# STM32H743.net
KiCad netlist of a schematic drawn in Altium Designer
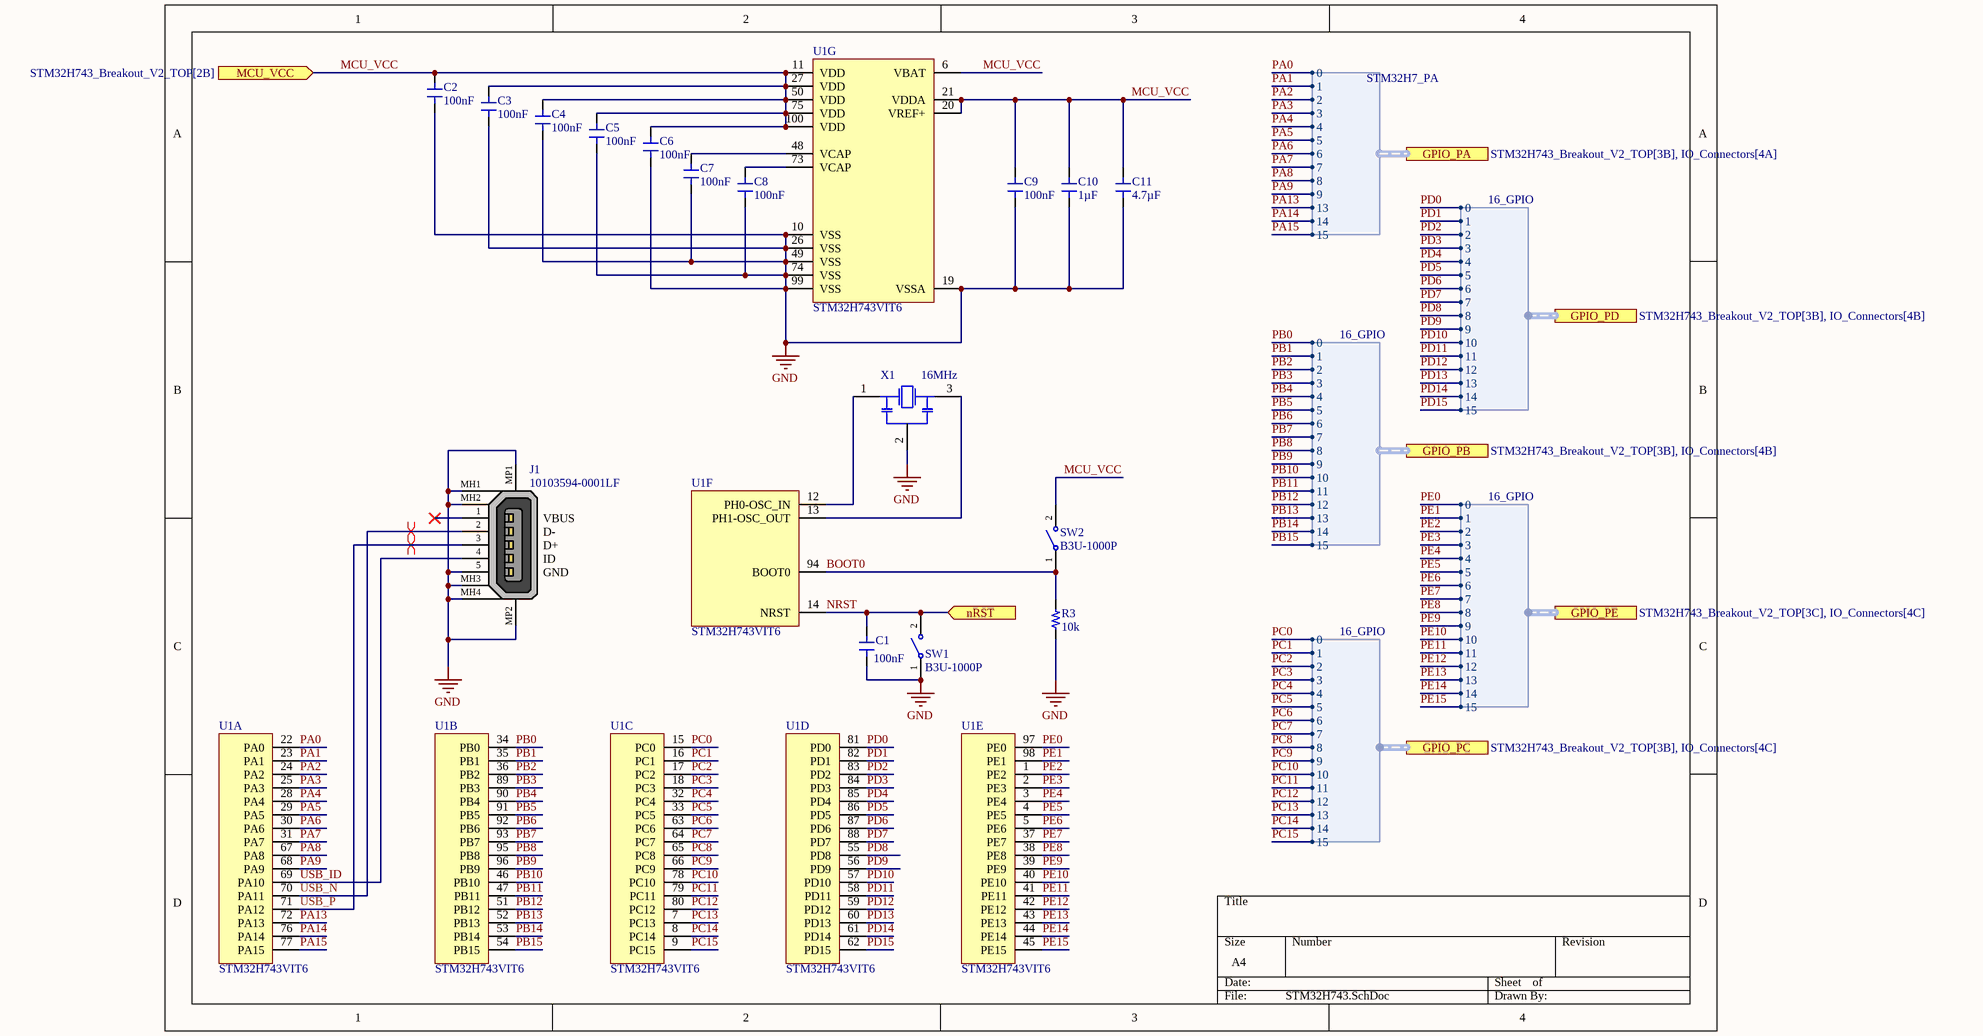
[diagram p0: STM32H743.SchDoc]

(export (version "E")
  (design (tool "Eeschema 10.0.6"))
  (components
    (comp (ref "C1")
      (value "C 0603 100nF 10% 50V X7R")
      (footprint "C-0603")
      (description "SMD Capacitor, Ceramic")
      (fields
        (field (name "CAPACITANCE") "100nF")
        (field (name "VOLTAGE") "50V")
        (field (name "TOLERANCE") "10%")
      )
      (libsource (lib "Project Rapid - Bruin Space") (part "Capacitor-NP"))
    )
    (comp (ref "C2")
      (value "C 0603 100nF 10% 50V X7R")
      (footprint "C-0603")
      (description "SMD Capacitor, Ceramic")
      (fields
        (field (name "CAPACITANCE") "100nF")
        (field (name "VOLTAGE") "50V")
        (field (name "TOLERANCE") "10%")
      )
      (libsource (lib "Project Rapid - Bruin Space") (part "Capacitor-NP"))
    )
    (comp (ref "C3")
      (value "C 0603 100nF 10% 50V X7R")
      (footprint "C-0603")
      (description "SMD Capacitor, Ceramic")
      (fields
        (field (name "CAPACITANCE") "100nF")
        (field (name "VOLTAGE") "50V")
        (field (name "TOLERANCE") "10%")
      )
      (libsource (lib "Project Rapid - Bruin Space") (part "Capacitor-NP"))
    )
    (comp (ref "C4")
      (value "C 0603 100nF 10% 50V X7R")
      (footprint "C-0603")
      (description "SMD Capacitor, Ceramic")
      (fields
        (field (name "CAPACITANCE") "100nF")
        (field (name "VOLTAGE") "50V")
        (field (name "TOLERANCE") "10%")
      )
      (libsource (lib "Project Rapid - Bruin Space") (part "Capacitor-NP"))
    )
    (comp (ref "C5")
      (value "C 0603 100nF 10% 50V X7R")
      (footprint "C-0603")
      (description "SMD Capacitor, Ceramic")
      (fields
        (field (name "CAPACITANCE") "100nF")
        (field (name "VOLTAGE") "50V")
        (field (name "TOLERANCE") "10%")
      )
      (libsource (lib "Project Rapid - Bruin Space") (part "Capacitor-NP"))
    )
    (comp (ref "C6")
      (value "C 0603 100nF 10% 50V X7R")
      (footprint "C-0603")
      (description "SMD Capacitor, Ceramic")
      (fields
        (field (name "CAPACITANCE") "100nF")
        (field (name "VOLTAGE") "50V")
        (field (name "TOLERANCE") "10%")
      )
      (libsource (lib "Project Rapid - Bruin Space") (part "Capacitor-NP"))
    )
    (comp (ref "C7")
      (value "C 0603 100nF 10% 50V X7R")
      (footprint "C-0603")
      (description "SMD Capacitor, Ceramic")
      (fields
        (field (name "CAPACITANCE") "100nF")
        (field (name "VOLTAGE") "50V")
        (field (name "TOLERANCE") "10%")
      )
      (libsource (lib "Project Rapid - Bruin Space") (part "Capacitor-NP"))
    )
    (comp (ref "C8")
      (value "C 0603 100nF 10% 50V X7R")
      (footprint "C-0603")
      (description "SMD Capacitor, Ceramic")
      (fields
        (field (name "CAPACITANCE") "100nF")
        (field (name "VOLTAGE") "50V")
        (field (name "TOLERANCE") "10%")
      )
      (libsource (lib "Project Rapid - Bruin Space") (part "Capacitor-NP"))
    )
    (comp (ref "C9")
      (value "C 0603 100nF 10% 50V X7R")
      (footprint "C-0603")
      (description "SMD Capacitor, Ceramic")
      (fields
        (field (name "CAPACITANCE") "100nF")
        (field (name "VOLTAGE") "50V")
        (field (name "TOLERANCE") "10%")
      )
      (libsource (lib "Project Rapid - Bruin Space") (part "Capacitor-NP"))
    )
    (comp (ref "C10")
      (value "C 0603 1µF 10% 50V X5R")
      (footprint "C-0603")
      (description "SMD Capacitor, Ceramic")
      (fields
        (field (name "CAPACITANCE") "1µF")
        (field (name "VOLTAGE") "50V")
        (field (name "TOLERANCE") "10%")
      )
      (libsource (lib "Project Rapid - Bruin Space") (part "Capacitor-NP"))
    )
    (comp (ref "C11")
      (value "C 0603 4.7µF 10% 16V X5R")
      (footprint "C-0603")
      (description "SMD Capacitor, Ceramic")
      (fields
        (field (name "CAPACITANCE") "4.7µF")
        (field (name "VOLTAGE") "16V")
        (field (name "TOLERANCE") "10%")
      )
      (libsource (lib "Project Rapid - Bruin Space") (part "Capacitor-NP"))
    )
    (comp (ref "J1")
      (value "10103594-0001LF")
      (footprint "10103594-0001LF")
      (description "USB 2.0 Micro-B, 5 leads, Through-Hole, Right Angle")
      (libsource (lib "Project Rapid - Bruin Space") (part "USB Micro-B Receptacle, 4 MH, 2 MP"))
    )
    (comp (ref "R3")
      (value "R 0603 10k 1% 0.100W 100PPM")
      (footprint "R-0603")
      (description "SMD Resistor, Thick Film")
      (fields (field (name "RESISTANCE") "10k") (field (name "TOLERANCE") "1%"))
      (libsource (lib "Project Rapid - Bruin Space") (part "Resistor"))
    )
    (comp (ref "SW1")
      (value "B3U-1000P")
      (footprint "B3U-1000P")
      (description "Tactile Switch, SPST-NO, 0.05A @ 12VDC, SMD")
      (libsource (lib "Project Rapid - Bruin Space") (part "Switch-SPST-NO"))
    )
    (comp (ref "SW2")
      (value "B3U-1000P")
      (footprint "B3U-1000P")
      (description "Tactile Switch, SPST-NO, 0.05A @ 12VDC, SMD")
      (libsource (lib "Project Rapid - Bruin Space") (part "Switch-SPST-NO"))
    )
    (comp (ref "U1")
      (value "STM32H743VIT6")
      (footprint "STM LQFP-100")
      (description "MCU 32-bit ARM Cortex M7 2MB Flash 3.3V 100-Pin LQFP")
      (libsource (lib "Project Rapid - Bruin Space") (part "STM32H743BIT6"))
    )
    (comp (ref "X1")
      (value "MURATA_CSTNE16M0V53C000R0")
      (footprint "MURATA_CSTNE16M0V53C000R0-Footprint-1")
      (description "Ceramic Resonator 16MHz 15pF SMD")
      (fields (field (name "FREQUENCY") "16MHz"))
      (libsource (lib "Project Rapid - Bruin Space") (part "Resonator-3PIN"))
    )
  )
  (nets
    (net (code "3") (name "/BOOT0") (class "Default")
      (node (ref "R3") (pin "2") (pinfunction "2_2") (pintype "passive"))
      (node (ref "SW2") (pin "1") (pinfunction "1_1") (pintype "passive"))
      (node (ref "U1") (pin "94") (pinfunction "BOOT0_94") (pintype "passive"))
    )
    (net (code "4") (name "/MCU_VCC") (class "Default")
      (node (ref "C10") (pin "2") (pinfunction "2_2") (pintype "passive"))
      (node (ref "C11") (pin "2") (pinfunction "2_2") (pintype "passive"))
      (node (ref "C2") (pin "2") (pinfunction "2_2") (pintype "passive"))
      (node (ref "C3") (pin "2") (pinfunction "2_2") (pintype "passive"))
      (node (ref "C4") (pin "2") (pinfunction "2_2") (pintype "passive"))
      (node (ref "C5") (pin "2") (pinfunction "2_2") (pintype "passive"))
      (node (ref "C6") (pin "2") (pinfunction "2_2") (pintype "passive"))
      (node (ref "C9") (pin "2") (pinfunction "2_2") (pintype "passive"))
      (node (ref "SW2") (pin "2") (pinfunction "2_2") (pintype "passive"))
      (node (ref "U1") (pin "100") (pinfunction "VDD_100") (pintype "passive"))
      (node (ref "U1") (pin "11") (pinfunction "VDD_11") (pintype "passive"))
      (node (ref "U1") (pin "20") (pinfunction "VREF+_20") (pintype "passive"))
      (node (ref "U1") (pin "21") (pinfunction "VDDA_21") (pintype "passive"))
      (node (ref "U1") (pin "27") (pinfunction "VDD_27") (pintype "passive"))
      (node (ref "U1") (pin "50") (pinfunction "VDD_50") (pintype "passive"))
      (node (ref "U1") (pin "6") (pinfunction "VBAT_6") (pintype "passive"))
      (node (ref "U1") (pin "75") (pinfunction "VDD_75") (pintype "passive"))
    )
    (net (code "5") (name "/NRST") (class "Default")
      (node (ref "C1") (pin "2") (pinfunction "2_2") (pintype "passive"))
      (node (ref "SW1") (pin "2") (pinfunction "2_2") (pintype "passive"))
      (node (ref "U1") (pin "14") (pinfunction "NRST_14") (pintype "passive"))
    )
    (net (code "6") (name "/PA0") (class "Default")
      (node (ref "U1") (pin "22") (pinfunction "PA0_22") (pintype "passive"))
    )
    (net (code "7") (name "/PA1") (class "Default")
      (node (ref "U1") (pin "23") (pinfunction "PA1_23") (pintype "passive"))
    )
    (net (code "8") (name "/PA2") (class "Default")
      (node (ref "U1") (pin "24") (pinfunction "PA2_24") (pintype "passive"))
    )
    (net (code "9") (name "/PA3") (class "Default")
      (node (ref "U1") (pin "25") (pinfunction "PA3_25") (pintype "passive"))
    )
    (net (code "10") (name "/PA4") (class "Default")
      (node (ref "U1") (pin "28") (pinfunction "PA4_28") (pintype "passive"))
    )
    (net (code "11") (name "/PA5") (class "Default")
      (node (ref "U1") (pin "29") (pinfunction "PA5_29") (pintype "passive"))
    )
    (net (code "12") (name "/PA6") (class "Default")
      (node (ref "U1") (pin "30") (pinfunction "PA6_30") (pintype "passive"))
    )
    (net (code "13") (name "/PA7") (class "Default")
      (node (ref "U1") (pin "31") (pinfunction "PA7_31") (pintype "passive"))
    )
    (net (code "14") (name "/PA8") (class "Default")
      (node (ref "U1") (pin "67") (pinfunction "PA8_67") (pintype "passive"))
    )
    (net (code "15") (name "/PA9") (class "Default")
      (node (ref "U1") (pin "68") (pinfunction "PA9_68") (pintype "passive"))
    )
    (net (code "16") (name "/PA13") (class "Default")
      (node (ref "U1") (pin "72") (pinfunction "PA13_72") (pintype "passive"))
    )
    (net (code "17") (name "/PA14") (class "Default")
      (node (ref "U1") (pin "76") (pinfunction "PA14_76") (pintype "passive"))
    )
    (net (code "18") (name "/PA15") (class "Default")
      (node (ref "U1") (pin "77") (pinfunction "PA15_77") (pintype "passive"))
    )
    (net (code "19") (name "/PB0") (class "Default")
      (node (ref "U1") (pin "34") (pinfunction "PB0_34") (pintype "passive"))
    )
    (net (code "20") (name "/PB1") (class "Default")
      (node (ref "U1") (pin "35") (pinfunction "PB1_35") (pintype "passive"))
    )
    (net (code "21") (name "/PB2") (class "Default")
      (node (ref "U1") (pin "36") (pinfunction "PB2_36") (pintype "passive"))
    )
    (net (code "22") (name "/PB3") (class "Default")
      (node (ref "U1") (pin "89") (pinfunction "PB3_89") (pintype "passive"))
    )
    (net (code "23") (name "/PB4") (class "Default")
      (node (ref "U1") (pin "90") (pinfunction "PB4_90") (pintype "passive"))
    )
    (net (code "24") (name "/PB5") (class "Default")
      (node (ref "U1") (pin "91") (pinfunction "PB5_91") (pintype "passive"))
    )
    (net (code "25") (name "/PB6") (class "Default")
      (node (ref "U1") (pin "92") (pinfunction "PB6_92") (pintype "passive"))
    )
    (net (code "26") (name "/PB7") (class "Default")
      (node (ref "U1") (pin "93") (pinfunction "PB7_93") (pintype "passive"))
    )
    (net (code "27") (name "/PB8") (class "Default")
      (node (ref "U1") (pin "95") (pinfunction "PB8_95") (pintype "passive"))
    )
    (net (code "28") (name "/PB9") (class "Default")
      (node (ref "U1") (pin "96") (pinfunction "PB9_96") (pintype "passive"))
    )
    (net (code "29") (name "/PB10") (class "Default")
      (node (ref "U1") (pin "46") (pinfunction "PB10_46") (pintype "passive"))
    )
    (net (code "30") (name "/PB11") (class "Default")
      (node (ref "U1") (pin "47") (pinfunction "PB11_47") (pintype "passive"))
    )
    (net (code "31") (name "/PB12") (class "Default")
      (node (ref "U1") (pin "51") (pinfunction "PB12_51") (pintype "passive"))
    )
    (net (code "32") (name "/PB13") (class "Default")
      (node (ref "U1") (pin "52") (pinfunction "PB13_52") (pintype "passive"))
    )
    (net (code "33") (name "/PB14") (class "Default")
      (node (ref "U1") (pin "53") (pinfunction "PB14_53") (pintype "passive"))
    )
    (net (code "34") (name "/PB15") (class "Default")
      (node (ref "U1") (pin "54") (pinfunction "PB15_54") (pintype "passive"))
    )
    (net (code "35") (name "/PC0") (class "Default")
      (node (ref "U1") (pin "15") (pinfunction "PC0_15") (pintype "passive"))
    )
    (net (code "36") (name "/PC1") (class "Default")
      (node (ref "U1") (pin "16") (pinfunction "PC1_16") (pintype "passive"))
    )
    (net (code "37") (name "/PC2") (class "Default")
      (node (ref "U1") (pin "17") (pinfunction "PC2_17") (pintype "passive"))
    )
    (net (code "38") (name "/PC3") (class "Default")
      (node (ref "U1") (pin "18") (pinfunction "PC3_18") (pintype "passive"))
    )
    (net (code "39") (name "/PC4") (class "Default")
      (node (ref "U1") (pin "32") (pinfunction "PC4_32") (pintype "passive"))
    )
    (net (code "40") (name "/PC5") (class "Default")
      (node (ref "U1") (pin "33") (pinfunction "PC5_33") (pintype "passive"))
    )
    (net (code "41") (name "/PC6") (class "Default")
      (node (ref "U1") (pin "63") (pinfunction "PC6_63") (pintype "passive"))
    )
    (net (code "42") (name "/PC7") (class "Default")
      (node (ref "U1") (pin "64") (pinfunction "PC7_64") (pintype "passive"))
    )
    (net (code "43") (name "/PC8") (class "Default")
      (node (ref "U1") (pin "65") (pinfunction "PC8_65") (pintype "passive"))
    )
    (net (code "44") (name "/PC9") (class "Default")
      (node (ref "U1") (pin "66") (pinfunction "PC9_66") (pintype "passive"))
    )
    (net (code "45") (name "/PC10") (class "Default")
      (node (ref "U1") (pin "78") (pinfunction "PC10_78") (pintype "passive"))
    )
    (net (code "46") (name "/PC11") (class "Default")
      (node (ref "U1") (pin "79") (pinfunction "PC11_79") (pintype "passive"))
    )
    (net (code "47") (name "/PC12") (class "Default")
      (node (ref "U1") (pin "80") (pinfunction "PC12_80") (pintype "passive"))
    )
    (net (code "48") (name "/PC13") (class "Default")
      (node (ref "U1") (pin "7") (pinfunction "PC13_7") (pintype "passive"))
    )
    (net (code "49") (name "/PC14") (class "Default")
      (node (ref "U1") (pin "8") (pinfunction "PC14_8") (pintype "passive"))
    )
    (net (code "50") (name "/PC15") (class "Default")
      (node (ref "U1") (pin "9") (pinfunction "PC15_9") (pintype "passive"))
    )
    (net (code "51") (name "/PD0") (class "Default")
      (node (ref "U1") (pin "81") (pinfunction "PD0_81") (pintype "passive"))
    )
    (net (code "52") (name "/PD1") (class "Default")
      (node (ref "U1") (pin "82") (pinfunction "PD1_82") (pintype "passive"))
    )
    (net (code "53") (name "/PD2") (class "Default")
      (node (ref "U1") (pin "83") (pinfunction "PD2_83") (pintype "passive"))
    )
    (net (code "54") (name "/PD3") (class "Default")
      (node (ref "U1") (pin "84") (pinfunction "PD3_84") (pintype "passive"))
    )
    (net (code "55") (name "/PD4") (class "Default")
      (node (ref "U1") (pin "85") (pinfunction "PD4_85") (pintype "passive"))
    )
    (net (code "56") (name "/PD5") (class "Default")
      (node (ref "U1") (pin "86") (pinfunction "PD5_86") (pintype "passive"))
    )
    (net (code "57") (name "/PD6") (class "Default")
      (node (ref "U1") (pin "87") (pinfunction "PD6_87") (pintype "passive"))
    )
    (net (code "58") (name "/PD7") (class "Default")
      (node (ref "U1") (pin "88") (pinfunction "PD7_88") (pintype "passive"))
    )
    (net (code "59") (name "/PD8") (class "Default")
      (node (ref "U1") (pin "55") (pinfunction "PD8_55") (pintype "passive"))
    )
    (net (code "60") (name "/PD9") (class "Default")
      (node (ref "U1") (pin "56") (pinfunction "PD9_56") (pintype "passive"))
    )
    (net (code "61") (name "/PD10") (class "Default")
      (node (ref "U1") (pin "57") (pinfunction "PD10_57") (pintype "passive"))
    )
    (net (code "62") (name "/PD11") (class "Default")
      (node (ref "U1") (pin "58") (pinfunction "PD11_58") (pintype "passive"))
    )
    (net (code "63") (name "/PD12") (class "Default")
      (node (ref "U1") (pin "59") (pinfunction "PD12_59") (pintype "passive"))
    )
    (net (code "64") (name "/PD13") (class "Default")
      (node (ref "U1") (pin "60") (pinfunction "PD13_60") (pintype "passive"))
    )
    (net (code "65") (name "/PD14") (class "Default")
      (node (ref "U1") (pin "61") (pinfunction "PD14_61") (pintype "passive"))
    )
    (net (code "66") (name "/PD15") (class "Default")
      (node (ref "U1") (pin "62") (pinfunction "PD15_62") (pintype "passive"))
    )
    (net (code "67") (name "/PE0") (class "Default")
      (node (ref "U1") (pin "97") (pinfunction "PE0_97") (pintype "passive"))
    )
    (net (code "68") (name "/PE1") (class "Default")
      (node (ref "U1") (pin "98") (pinfunction "PE1_98") (pintype "passive"))
    )
    (net (code "69") (name "/PE2") (class "Default")
      (node (ref "U1") (pin "1") (pinfunction "PE2_1") (pintype "passive"))
    )
    (net (code "70") (name "/PE3") (class "Default")
      (node (ref "U1") (pin "2") (pinfunction "PE3_2") (pintype "passive"))
    )
    (net (code "71") (name "/PE4") (class "Default")
      (node (ref "U1") (pin "3") (pinfunction "PE4_3") (pintype "passive"))
    )
    (net (code "72") (name "/PE5") (class "Default")
      (node (ref "U1") (pin "4") (pinfunction "PE5_4") (pintype "passive"))
    )
    (net (code "73") (name "/PE6") (class "Default")
      (node (ref "U1") (pin "5") (pinfunction "PE6_5") (pintype "passive"))
    )
    (net (code "74") (name "/PE7") (class "Default")
      (node (ref "U1") (pin "37") (pinfunction "PE7_37") (pintype "passive"))
    )
    (net (code "75") (name "/PE8") (class "Default")
      (node (ref "U1") (pin "38") (pinfunction "PE8_38") (pintype "passive"))
    )
    (net (code "76") (name "/PE9") (class "Default")
      (node (ref "U1") (pin "39") (pinfunction "PE9_39") (pintype "passive"))
    )
    (net (code "77") (name "/PE10") (class "Default")
      (node (ref "U1") (pin "40") (pinfunction "PE10_40") (pintype "passive"))
    )
    (net (code "78") (name "/PE11") (class "Default")
      (node (ref "U1") (pin "41") (pinfunction "PE11_41") (pintype "passive"))
    )
    (net (code "79") (name "/PE12") (class "Default")
      (node (ref "U1") (pin "42") (pinfunction "PE12_42") (pintype "passive"))
    )
    (net (code "80") (name "/PE13") (class "Default")
      (node (ref "U1") (pin "43") (pinfunction "PE13_43") (pintype "passive"))
    )
    (net (code "81") (name "/PE14") (class "Default")
      (node (ref "U1") (pin "44") (pinfunction "PE14_44") (pintype "passive"))
    )
    (net (code "82") (name "/PE15") (class "Default")
      (node (ref "U1") (pin "45") (pinfunction "PE15_45") (pintype "passive"))
    )
    (net (code "83") (name "/USB_ID") (class "Default")
      (node (ref "J1") (pin "4") (pinfunction "ID_4") (pintype "passive"))
      (node (ref "U1") (pin "69") (pinfunction "PA10_69") (pintype "passive"))
    )
    (net (code "84") (name "/USB_N") (class "Default")
      (node (ref "J1") (pin "2") (pinfunction "D-_2") (pintype "passive"))
      (node (ref "U1") (pin "70") (pinfunction "PA11_70") (pintype "passive"))
    )
    (net (code "85") (name "/USB_P") (class "Default")
      (node (ref "J1") (pin "3") (pinfunction "D+_3") (pintype "passive"))
      (node (ref "U1") (pin "71") (pinfunction "PA12_71") (pintype "passive"))
    )
    (net (code "88") (name "GND") (class "Default")
      (node (ref "C1") (pin "1") (pinfunction "1_1") (pintype "passive"))
      (node (ref "C10") (pin "1") (pinfunction "1_1") (pintype "passive"))
      (node (ref "C11") (pin "1") (pinfunction "1_1") (pintype "passive"))
      (node (ref "C2") (pin "1") (pinfunction "1_1") (pintype "passive"))
      (node (ref "C3") (pin "1") (pinfunction "1_1") (pintype "passive"))
      (node (ref "C4") (pin "1") (pinfunction "1_1") (pintype "passive"))
      (node (ref "C5") (pin "1") (pinfunction "1_1") (pintype "passive"))
      (node (ref "C6") (pin "1") (pinfunction "1_1") (pintype "passive"))
      (node (ref "C7") (pin "1") (pinfunction "1_1") (pintype "passive"))
      (node (ref "C8") (pin "1") (pinfunction "1_1") (pintype "passive"))
      (node (ref "C9") (pin "1") (pinfunction "1_1") (pintype "passive"))
      (node (ref "J1") (pin "5") (pinfunction "GND_5") (pintype "passive"))
      (node (ref "J1") (pin "MH1") (pinfunction "MH1_MH1") (pintype "passive"))
      (node (ref "J1") (pin "MH2") (pinfunction "MH2_MH2") (pintype "passive"))
      (node (ref "J1") (pin "MH3") (pinfunction "MH3_MH3") (pintype "passive"))
      (node (ref "J1") (pin "MH4") (pinfunction "MH4_MH4") (pintype "passive"))
      (node (ref "J1") (pin "MP1") (pinfunction "MP1_MP1") (pintype "passive"))
      (node (ref "J1") (pin "MP2") (pinfunction "MP2_MP2") (pintype "passive"))
      (node (ref "R3") (pin "1") (pinfunction "1_1") (pintype "passive"))
      (node (ref "SW1") (pin "1") (pinfunction "1_1") (pintype "passive"))
      (node (ref "U1") (pin "10") (pinfunction "VSS_10") (pintype "passive"))
      (node (ref "U1") (pin "19") (pinfunction "VSSA_19") (pintype "passive"))
      (node (ref "U1") (pin "26") (pinfunction "VSS_26") (pintype "passive"))
      (node (ref "U1") (pin "49") (pinfunction "VSS_49") (pintype "passive"))
      (node (ref "U1") (pin "74") (pinfunction "VSS_74") (pintype "passive"))
      (node (ref "U1") (pin "99") (pinfunction "VSS_99") (pintype "passive"))
      (node (ref "X1") (pin "2") (pinfunction "GND_2") (pintype "passive"))
    )
    (net (code "89") (name "Net-(C7-Pad2)") (class "Default")
      (node (ref "C7") (pin "2") (pinfunction "2_2") (pintype "passive"))
      (node (ref "U1") (pin "48") (pinfunction "VCAP_48") (pintype "passive"))
    )
    (net (code "90") (name "Net-(C8-Pad2)") (class "Default")
      (node (ref "C8") (pin "2") (pinfunction "2_2") (pintype "passive"))
      (node (ref "U1") (pin "73") (pinfunction "VCAP_73") (pintype "passive"))
    )
    (net (code "91") (name "Net-(U1F-PH0-OSC_IN)") (class "Default")
      (node (ref "U1") (pin "12") (pinfunction "PH0-OSC_IN_12") (pintype "passive"))
      (node (ref "X1") (pin "1") (pinfunction "A_1") (pintype "passive"))
    )
    (net (code "92") (name "Net-(U1F-PH1-OSC_OUT)") (class "Default")
      (node (ref "U1") (pin "13") (pinfunction "PH1-OSC_OUT_13") (pintype "passive"))
      (node (ref "X1") (pin "3") (pinfunction "B_3") (pintype "passive"))
    )
    (net (code "93") (name "unconnected-(J1-VBUS-Pad1)") (class "Default")
      (node (ref "J1") (pin "1") (pinfunction "VBUS_1") (pintype "passive+no_connect"))
    )
  )
)
